# SCH_led_button_2026-04-27.net
KiCad netlist of a schematic drawn in EasyEDA
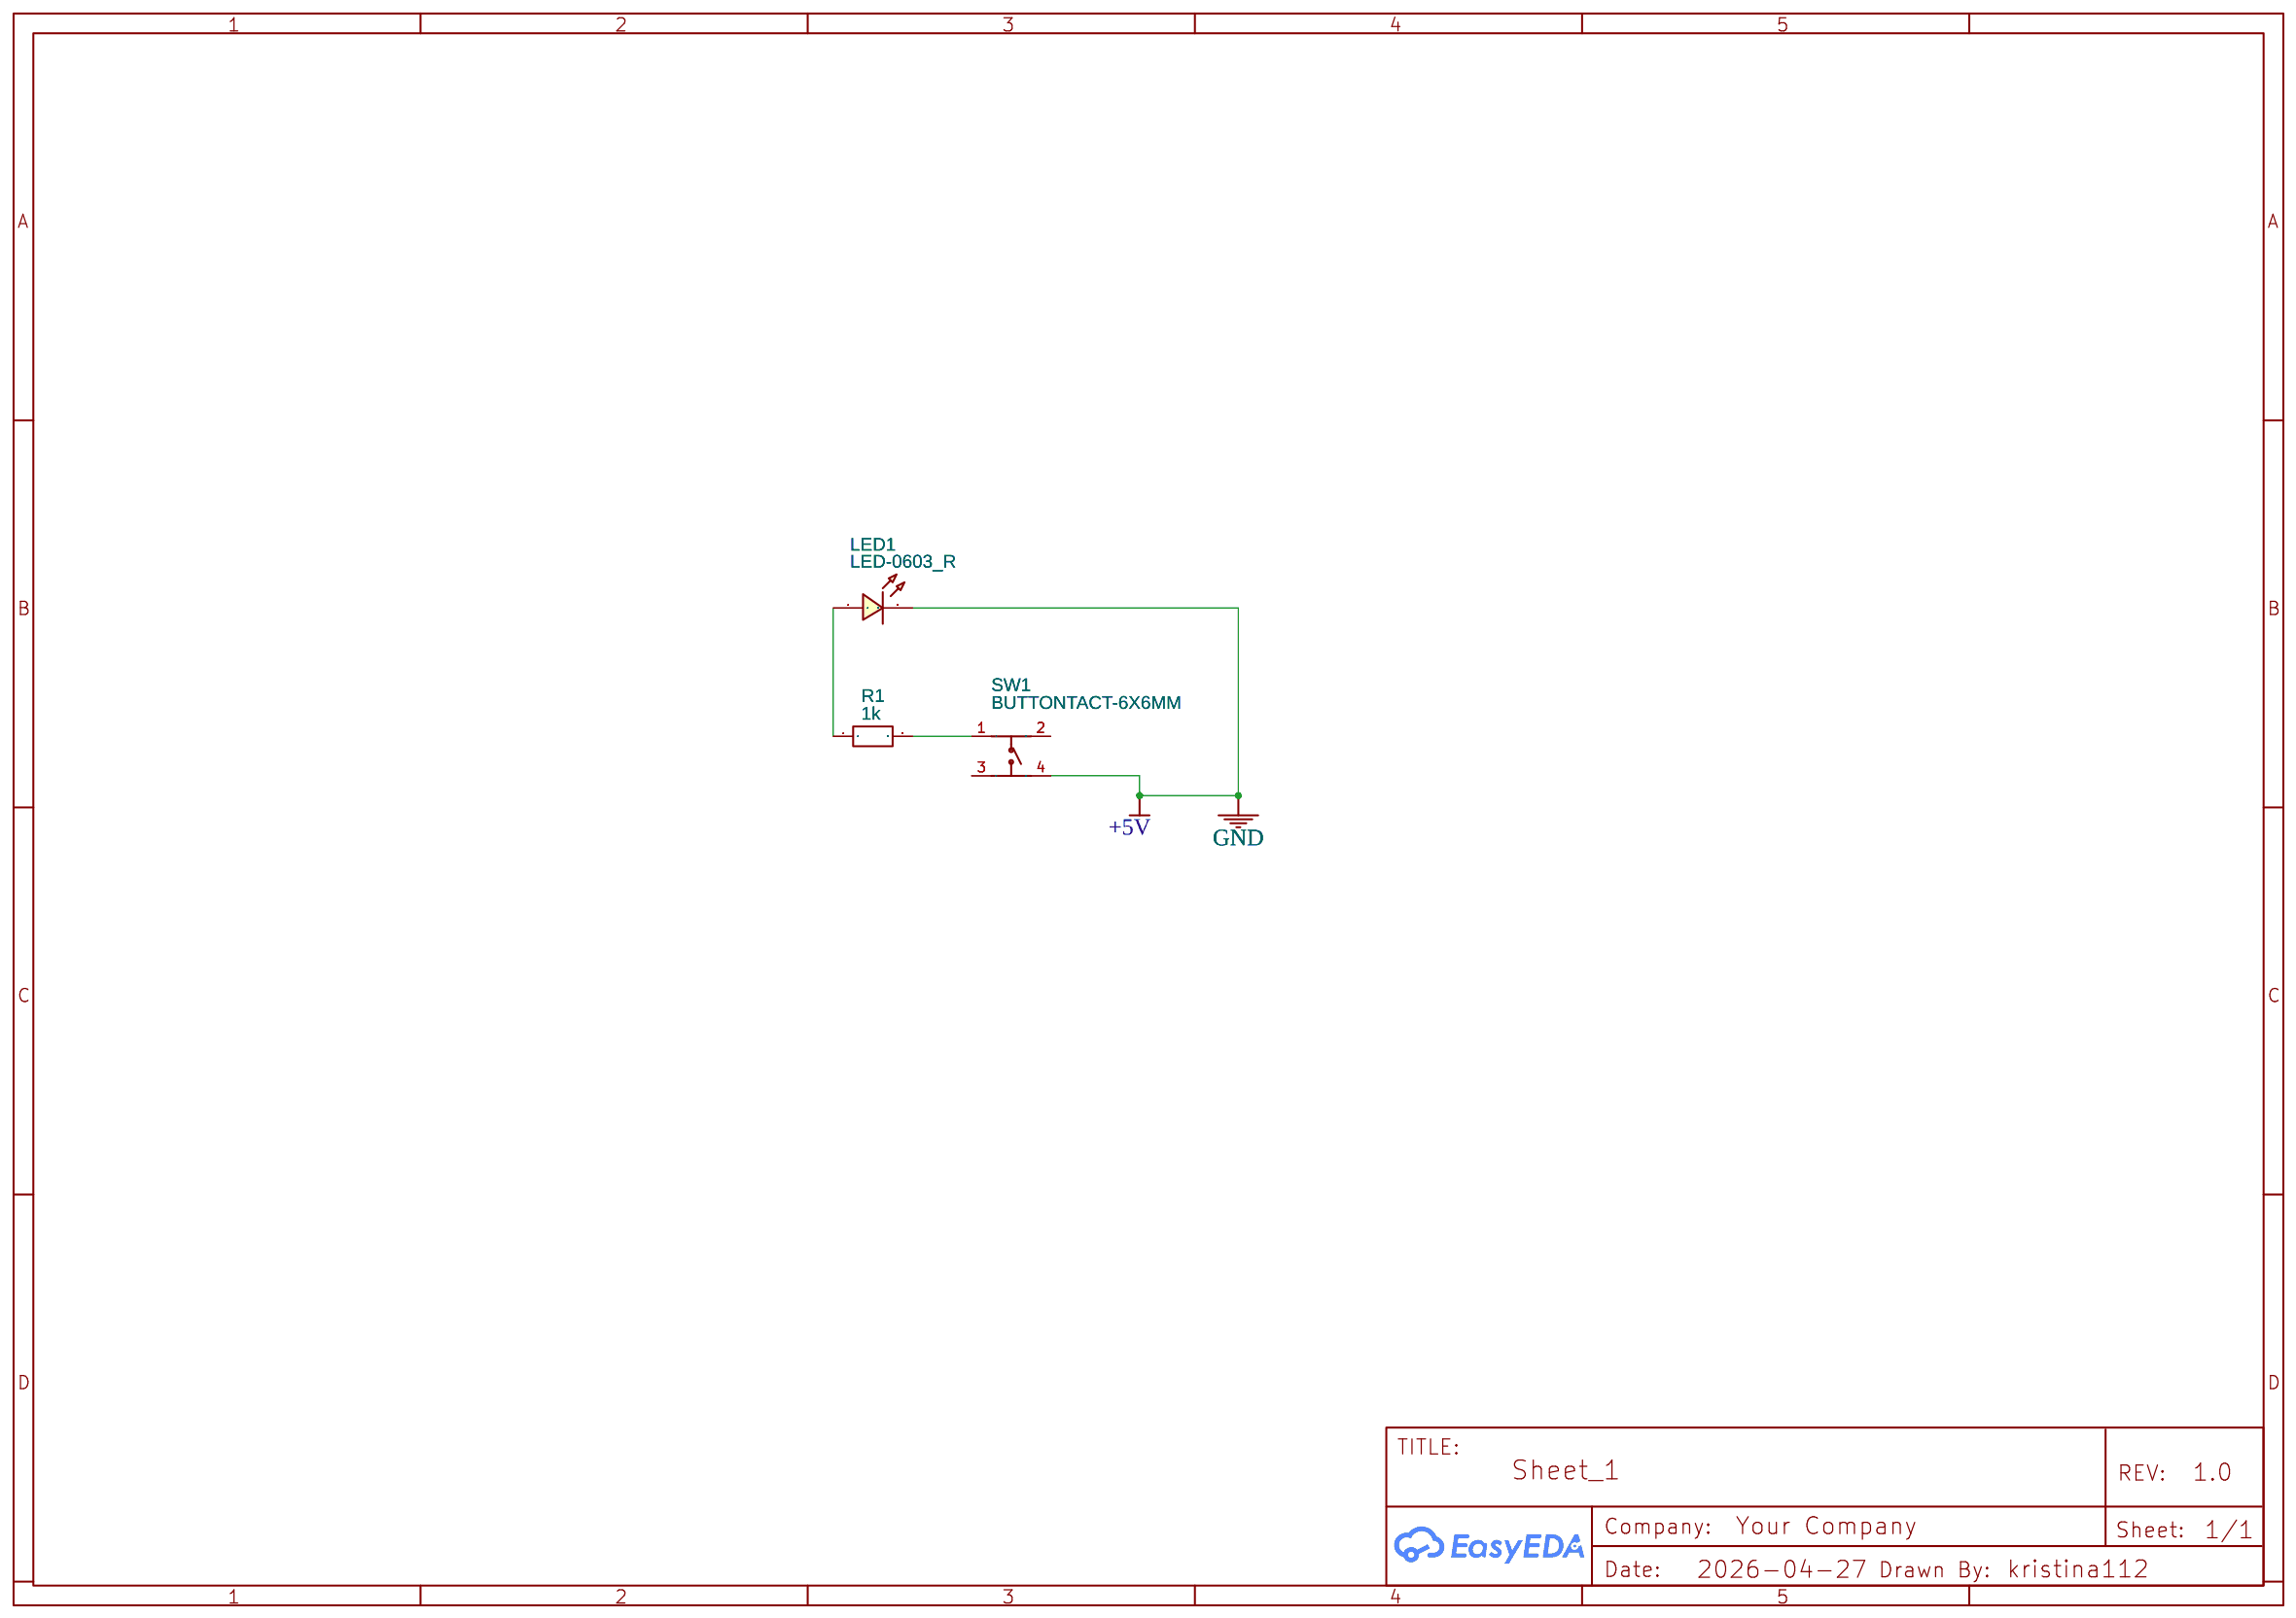
[diagram p0: schematic sheet]

(export (version "E")
  (design (tool "Eeschema 10.0.6"))
  (components
    (comp (ref "LED1")
      (value "LED-0603_R")
      (fields
        (field (name "Manufacturer Part") "19-217/R6C-AL1M2VY/3T")
        (field (name "Manufacturer") "EVERLIGHT(台湾亿光)")
      )
      (libsource (lib "") (part "LED-0603_R"))
    )
    (comp (ref "R1") (value "1k") (libsource (lib "") (part "R_0603_EU")))
    (comp (ref "SW1")
      (value "BUTTONTACT-6X6MM")
      (fields (field (name "Manufacturer Part") "Buttontact-6x6mm"))
      (libsource (lib "") (part "BUTTONTACT-6X6MM"))
    )
  )
  (nets
    (net (code "1") (name "+5V") (class "Default")
      (node (ref "LED1") (pin "2") (pinfunction "2_2") (pintype "unspecified"))
      (node (ref "SW1") (pin "4") (pinfunction "D_4") (pintype "unspecified"))
    )
    (net (code "2") (name "Net-(LED1-Pad1)") (class "Default")
      (node (ref "LED1") (pin "1") (pinfunction "1_1") (pintype "unspecified"))
      (node (ref "R1") (pin "1") (pinfunction "1_1") (pintype "unspecified"))
    )
    (net (code "3") (name "Net-(SW1-A)") (class "Default")
      (node (ref "R1") (pin "2") (pinfunction "2_2") (pintype "unspecified"))
      (node (ref "SW1") (pin "1") (pinfunction "A_1") (pintype "unspecified"))
    )
    (net (code "4") (name "unconnected-(SW1-B-Pad2)") (class "Default")
      (node (ref "SW1") (pin "2") (pinfunction "B_2") (pintype "unspecified"))
    )
    (net (code "5") (name "unconnected-(SW1-C-Pad3)") (class "Default")
      (node (ref "SW1") (pin "3") (pinfunction "C_3") (pintype "unspecified"))
    )
  )
)
